# Synch_Demod.net
KiCad netlist of a schematic drawn in Altium Designer
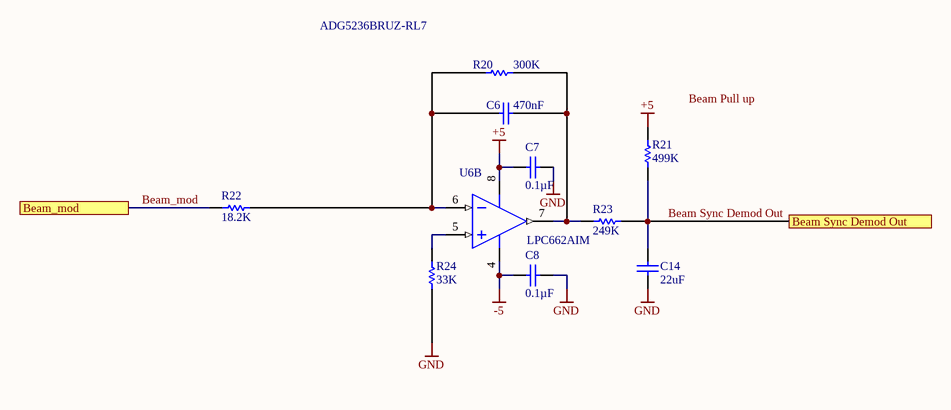
[diagram p0: Synch_Demod.SchDoc]

(export (version "E")
  (design (tool "Eeschema 10.0.6"))
  (components
    (comp (ref "C6")
      (value "470nF")
      (footprint "CAPC0805(2012)75_L")
      (description "CAP CER 0.47UF 25V X7R 0805")
      (fields
        (field (name "MANUFACTURER") "Murata Electronics North America")
        (field (name "MANUFACTURER PART NUMBER") "GRM219R71E474KA88D")
      )
      (libsource (lib "Altium Content Vault") (part "CMP-1036-02117-1"))
    )
    (comp (ref "C7")
      (value "CAP CER 0.1UF 25V X7R 0805")
      (footprint "CAPC0805(2012)145_N")
      (fields
        (field (name "MANUFACTURER") "Murata Electronics North America")
        (field (name "MANUFACTURER PART NUMBER") "GRM21BR71E104KA01L")
        (field (name "CAPACITANCE") "0.1µF")
        (field (name "TOLERANCE") "±10%")
      )
      (libsource (lib "Altium Content Vault") (part "CMP-1036-04795-1"))
    )
    (comp (ref "C8")
      (value "CAP CER 0.1UF 25V X7R 0805")
      (footprint "CAPC0805(2012)145_N")
      (fields
        (field (name "MANUFACTURER") "Murata Electronics North America")
        (field (name "MANUFACTURER PART NUMBER") "GRM21BR71E104KA01L")
        (field (name "CAPACITANCE") "0.1µF")
        (field (name "TOLERANCE") "±10%")
      )
      (libsource (lib "Altium Content Vault") (part "CMP-1036-04795-1"))
    )
    (comp (ref "C14")
      (value "22uF")
      (footprint "CAPC0805(2012)75_L")
      (description "CAP CER 22UF 25V X5R 0805")
      (fields
        (field (name "MANUFACTURER") "Murata Electronics North America")
        (field (name "MANUFACTURER PART NUMBER") "GRM21BR61E226ME44L")
      )
      (libsource (lib "Altium Content Vault") (part "CMP-1036-02117-1"))
    )
    (comp (ref "R20")
      (value "300K")
      (footprint "RESC0805(2012)_L")
      (description "RES SMD 300K OHM 1% 1/8W 0805")
      (fields
        (field (name "MANUFACTURER") "Vishay Dale")
        (field (name "MANUFACTURER PART NUMBER") "CRCW0805300KFKEAHP")
      )
      (libsource (lib "Altium Content Vault") (part "CMP-1013-00215-1"))
    )
    (comp (ref "R21")
      (value "499K")
      (footprint "RESC0805(2012)_L")
      (description "RES SMD 499K OHM 0.1% 1/8W 0805")
      (fields
        (field (name "MANUFACTURER") "Panasonic Electronic Components")
        (field (name "MANUFACTURER PART NUMBER") "ERA-6AEB4993V")
      )
      (libsource (lib "Altium Content Vault") (part "CMP-1013-00215-1"))
    )
    (comp (ref "R22")
      (value "18.2K")
      (footprint "RESC0805(2012)_L")
      (description "RES SMD 18.2K OHM 1% 1/8W 0805")
      (fields
        (field (name "MANUFACTURER") "Panasonic Electronic Components")
        (field (name "MANUFACTURER PART NUMBER") "ERJ-6ENF1822V")
      )
      (libsource (lib "Altium Content Vault") (part "CMP-1013-00215-1"))
    )
    (comp (ref "R23")
      (value "249K")
      (footprint "RESC0805(2012)_L")
      (description "RES SMD 249K OHM 0.1% 1/8W 0805")
      (fields
        (field (name "MANUFACTURER") "Panasonic Electronic Components")
        (field (name "MANUFACTURER PART NUMBER") "ERA-6AEB2493V")
      )
      (libsource (lib "Altium Content Vault") (part "CMP-1013-00215-1"))
    )
    (comp (ref "R24")
      (value "33K")
      (footprint "RESC0805(2012)_L")
      (description "RES SMD 33K OHM 1% 1/2W 0805")
      (fields
        (field (name "MANUFACTURER") "Vishay Dale")
        (field (name "MANUFACTURER PART NUMBER") "CRCW080533K0FKEAHP")
      )
      (libsource (lib "Altium Content Vault") (part "CMP-1013-00215-1"))
    )
    (comp (ref "U6")
      (value "LPC662AIM")
      (footprint "D0008A_M")
      (description "Low Power CMOS Dual Operational Amplifier, 8-pin Narrow SOIC")
      (fields
        (field (name "MANUFACTURER") "Texas Instruments")
        (field (name "MANUFACTURER PART NUMBER") "LPC662AIM/NOPB")
      )
      (libsource (lib "Altium Content Vault") (part "CMP-0055-00867-3"))
    )
  )
  (nets
    (net (code "1") (name "+5") (class "Default")
      (node (ref "C7") (pin "1") (pinfunction "1_1") (pintype "passive"))
      (node (ref "R21") (pin "2") (pinfunction "2_2") (pintype "passive"))
      (node (ref "U6") (pin "8") (pinfunction "V+_8") (pintype "power_in"))
    )
    (net (code "2") (name "-5") (class "Default")
      (node (ref "C8") (pin "1") (pinfunction "1_1") (pintype "passive"))
      (node (ref "U6") (pin "4") (pinfunction "V-_4") (pintype "power_in"))
    )
    (net (code "4") (name "/Beam Sync Demod Out") (class "Default")
      (node (ref "C14") (pin "2") (pinfunction "2_2") (pintype "passive"))
      (node (ref "R21") (pin "1") (pinfunction "1_1") (pintype "passive"))
      (node (ref "R23") (pin "1") (pinfunction "1_1") (pintype "passive"))
    )
    (net (code "5") (name "/Beam_mod") (class "Default")
      (node (ref "R22") (pin "2") (pinfunction "2_2") (pintype "passive"))
    )
    (net (code "6") (name "GND") (class "Default")
      (node (ref "C14") (pin "1") (pinfunction "1_1") (pintype "passive"))
      (node (ref "C7") (pin "2") (pinfunction "2_2") (pintype "passive"))
      (node (ref "C8") (pin "2") (pinfunction "2_2") (pintype "passive"))
      (node (ref "R24") (pin "1") (pinfunction "1_1") (pintype "passive"))
    )
    (net (code "7") (name "Net-(U6B-INB+)") (class "Default")
      (node (ref "R24") (pin "2") (pinfunction "2_2") (pintype "passive"))
      (node (ref "U6") (pin "5") (pinfunction "INB+_5") (pintype "input"))
    )
    (net (code "8") (name "Net-(U6B-INB-)") (class "Default")
      (node (ref "C6") (pin "1") (pinfunction "1_1") (pintype "passive"))
      (node (ref "R20") (pin "2") (pinfunction "2_2") (pintype "passive"))
      (node (ref "R22") (pin "1") (pinfunction "1_1") (pintype "passive"))
      (node (ref "U6") (pin "6") (pinfunction "INB-_6") (pintype "input"))
    )
    (net (code "9") (name "Net-(U6B-OUTB)") (class "Default")
      (node (ref "C6") (pin "2") (pinfunction "2_2") (pintype "passive"))
      (node (ref "R20") (pin "1") (pinfunction "1_1") (pintype "passive"))
      (node (ref "R23") (pin "2") (pinfunction "2_2") (pintype "passive"))
      (node (ref "U6") (pin "7") (pinfunction "OUTB_7") (pintype "output"))
    )
  )
)
